# PMV2_IBV1_Altium_page01.net
KiCad netlist of a schematic drawn in Altium Designer
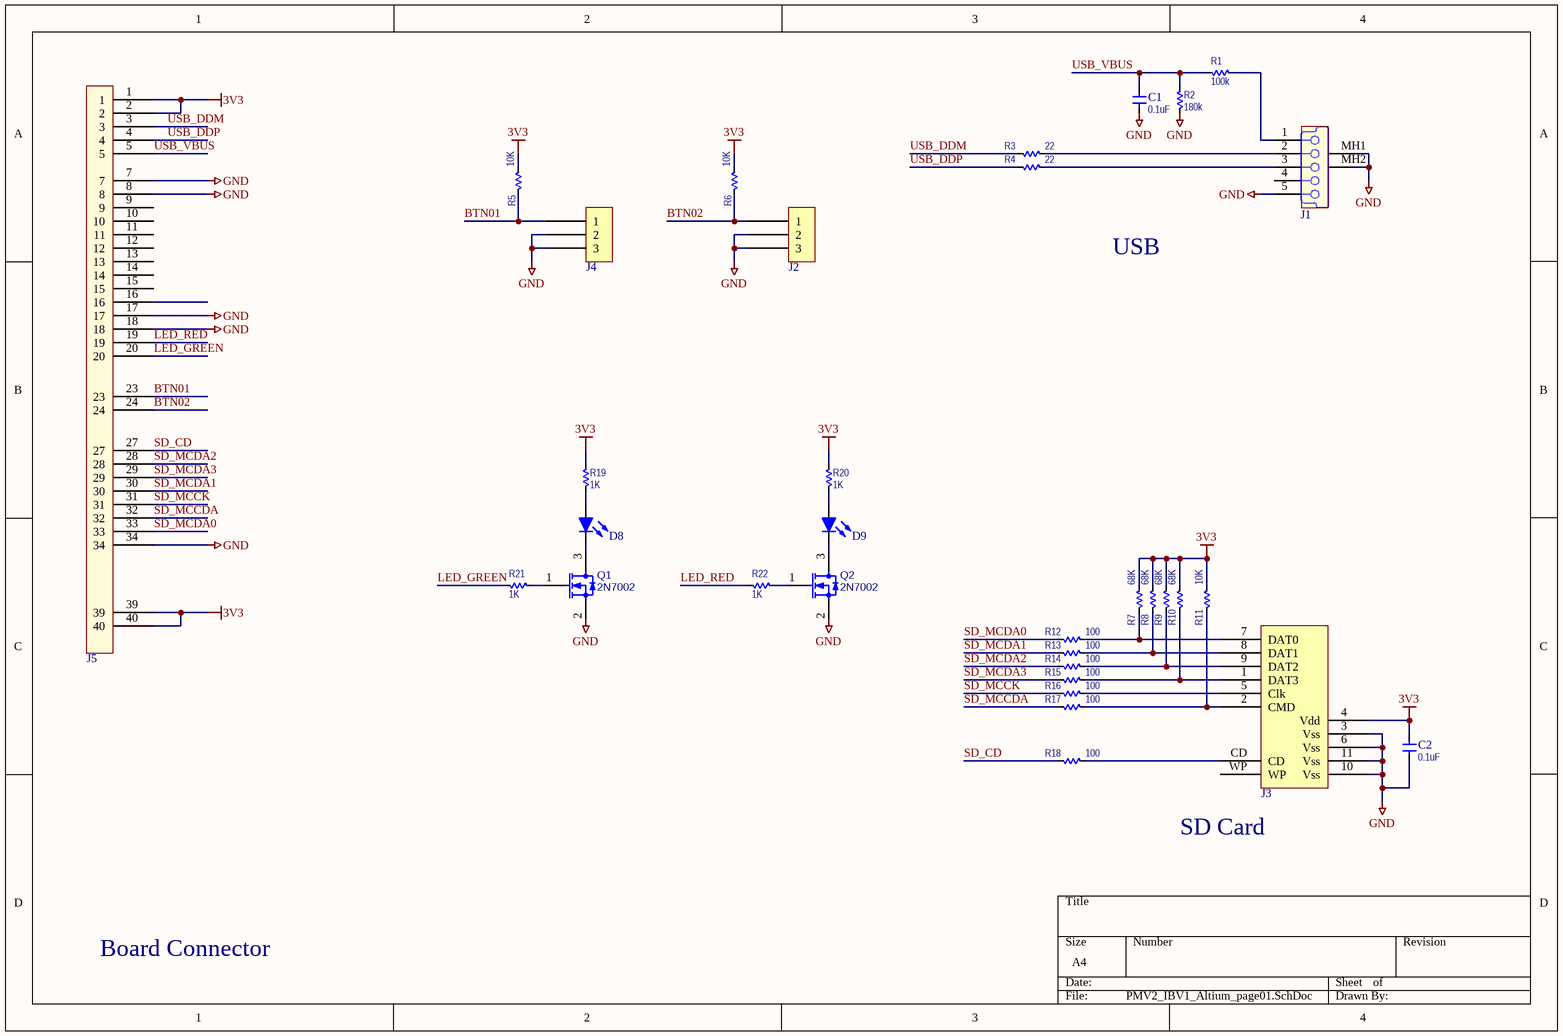
[diagram p0: PMV2_IBV1_Altium_page01.SchDoc]

(export (version "E")
  (design (tool "Eeschema 10.0.6"))
  (components
    (comp (ref "C1")
      (value "0.1uF")
      (footprint "CAPC3216X135N_B")
      (description "CAP CER 0.1UF 25V X7R 1206")
      (fields (field (name "MANUFACTURER") "Kemet") (field (name "DIGIKEY PART NUMBER") "399-5615-1-ND"))
      (libsource (lib "lib_ic_CAP") (part "CAP_C1206F104K3RACTU_KEMET"))
    )
    (comp (ref "C2")
      (value "0.1uF")
      (footprint "CAPC3216X135N_B")
      (description "CAP CER 0.1UF 25V X7R 1206")
      (fields (field (name "MANUFACTURER") "Kemet") (field (name "DIGIKEY PART NUMBER") "399-5615-1-ND"))
      (libsource (lib "lib_ic_CAP") (part "CAP_C1206F104K3RACTU_KEMET"))
    )
    (comp (ref "D8")
      (value "DIO_LED")
      (footprint "Led")
      (description "Diode Led")
      (fields (field (name "PUBLISHER") "Altium Limited"))
      (libsource (lib "lib_ic_DIO") (part "DIO_LED"))
    )
    (comp (ref "D9")
      (value "DIO_LED")
      (footprint "Led")
      (description "Diode Led")
      (fields (field (name "PUBLISHER") "Altium Limited"))
      (libsource (lib "lib_ic_DIO") (part "DIO_LED"))
    )
    (comp (ref "J1")
      (value "CON_MINI_USB")
      (footprint "UBS MiniB")
      (fields
        (field (name "DIGIKEY PART NUMBER") "H11589CT-ND")
        (field (name "MANUFACTURER PART NUMBER") "UX60SC-MB-5S8")
        (field (name "MOUSER PART NUMBER") "798-UX60SC-MB-5S8")
      )
      (libsource (lib "lib_ic_CON") (part "CON_MINI_USB"))
    )
    (comp (ref "J2")
      (value "MSC_Switch")
      (footprint "SW_FSMRA3JH")
      (libsource (lib "lib_ic_MSC") (part "MSC_Switch"))
    )
    (comp (ref "J3")
      (value "CON_SD_Socket")
      (footprint "SD CARD SOCKET")
      (description "SD Socket")
      (fields
        (field (name "DIGIKEY PART NUMBER") "609-3956-1-ND")
        (field (name "MANUFACTURER PART NUMBER") "10067847-001RLF")
      )
      (libsource (lib "lib_ic_CON") (part "CON_SD_Socket"))
    )
    (comp (ref "J4")
      (value "MSC_Switch")
      (footprint "SW_FSMRA3JH")
      (libsource (lib "lib_ic_MSC") (part "MSC_Switch"))
    )
    (comp (ref "J5")
      (value "CON_Header_2x30_PMV2")
      (footprint "HeaderX70b")
      (libsource (lib "lib_ic_CON") (part "CON_Header_2x30_PMV2"))
    )
    (comp (ref "Q1")
      (value "2N7002")
      (footprint "SOT23-3M")
      (description "MOSFET N-CH 60V 115MA SOT23-3")
      (fields
        (field (name "MOUSER PART NUMBER") "621-2N7002-F")
        (field (name "DIGIKEY PART NUMBER") "2N7002-7-F")
      )
      (libsource (lib "lib_ic_IC") (part "Q_2N7002-7-F_DIODES"))
    )
    (comp (ref "Q2")
      (value "2N7002")
      (footprint "SOT23-3M")
      (description "MOSFET N-CH 60V 115MA SOT23-3")
      (fields
        (field (name "MOUSER PART NUMBER") "621-2N7002-F")
        (field (name "DIGIKEY PART NUMBER") "2N7002-7-F")
      )
      (libsource (lib "lib_ic_IC") (part "Q_2N7002-7-F_DIODES"))
    )
    (comp (ref "R1")
      (value "100k")
      (footprint "RESC3216N")
      (description "RES SMD 100K OHM 5% 1/4W 1206")
      (fields (field (name "MANUFACTURER") "YAGEO") (field (name "DIGIKEY PART NUMBER") "311-100KERCT-ND"))
      (libsource (lib "lib_ic_RES") (part "RES_RC1206JR-07100KL_YAGEO"))
    )
    (comp (ref "R2")
      (value "180k")
      (footprint "RESC3216N")
      (description "RES SMD 180K OHM 5% 1/4W 1206")
      (fields (field (name "MANUFACTURER") "YAGEO") (field (name "DIGIKEY PART NUMBER") "311-180KERCT-ND"))
      (libsource (lib "lib_ic_RES") (part "RES_RC1206JR-07180KL_YAGEO"))
    )
    (comp (ref "R3")
      (value "22")
      (footprint "RESC3216N")
      (description "RES SMD 22 OHM 5% 1/4W 1206")
      (fields (field (name "MANUFACTURER") "YAGEO") (field (name "DIGIKEY PART NUMBER") "311-22ERCT-ND"))
      (libsource (lib "lib_ic_RES") (part "RES_RC1206JR-0722RL_YAGEO"))
    )
    (comp (ref "R4")
      (value "22")
      (footprint "RESC3216N")
      (description "RES SMD 22 OHM 5% 1/4W 1206")
      (fields (field (name "MANUFACTURER") "YAGEO") (field (name "DIGIKEY PART NUMBER") "311-22ERCT-ND"))
      (libsource (lib "lib_ic_RES") (part "RES_RC1206JR-0722RL_YAGEO"))
    )
    (comp (ref "R5")
      (value "10K")
      (footprint "RESC3216N")
      (description "RES SMD 10K OHM 1% 1/4W 1206")
      (fields (field (name "TOLERANCE") "1%") (field (name "MANUFACTURER") "Yageo"))
      (libsource (lib "lib_ic_RES") (part "RES_RC1206FR-0710KL_Yageo"))
    )
    (comp (ref "R6")
      (value "10K")
      (footprint "RESC3216N")
      (description "RES SMD 10K OHM 1% 1/4W 1206")
      (fields (field (name "TOLERANCE") "1%") (field (name "MANUFACTURER") "Yageo"))
      (libsource (lib "lib_ic_RES") (part "RES_RC1206FR-0710KL_Yageo"))
    )
    (comp (ref "R7")
      (value "68K")
      (footprint "RESC3216N")
      (description "RES SMD 68K OHM 5% 1/4W 1206")
      (fields (field (name "TOLERANCE") "5%") (field (name "MANUFACTURER") "Yageo"))
      (libsource (lib "lib_ic_RES") (part "RES_RC1206JR-0768KL_Yageo"))
    )
    (comp (ref "R8")
      (value "68K")
      (footprint "RESC3216N")
      (description "RES SMD 68K OHM 5% 1/4W 1206")
      (fields (field (name "TOLERANCE") "5%") (field (name "MANUFACTURER") "Yageo"))
      (libsource (lib "lib_ic_RES") (part "RES_RC1206JR-0768KL_Yageo"))
    )
    (comp (ref "R9")
      (value "68K")
      (footprint "RESC3216N")
      (description "RES SMD 68K OHM 5% 1/4W 1206")
      (fields (field (name "TOLERANCE") "5%") (field (name "MANUFACTURER") "Yageo"))
      (libsource (lib "lib_ic_RES") (part "RES_RC1206JR-0768KL_Yageo"))
    )
    (comp (ref "R10")
      (value "68K")
      (footprint "RESC3216N")
      (description "RES SMD 68K OHM 5% 1/4W 1206")
      (fields (field (name "TOLERANCE") "5%") (field (name "MANUFACTURER") "Yageo"))
      (libsource (lib "lib_ic_RES") (part "RES_RC1206JR-0768KL_Yageo"))
    )
    (comp (ref "R11")
      (value "10K")
      (footprint "RESC3216N")
      (description "RES SMD 10K OHM 1% 1/4W 1206")
      (fields (field (name "TOLERANCE") "1%") (field (name "MANUFACTURER") "Yageo"))
      (libsource (lib "lib_ic_RES") (part "RES_RC1206FR-0710KL_Yageo"))
    )
    (comp (ref "R12")
      (value "100")
      (footprint "RESC3216N")
      (description "RES SMD 100 OHM 5% 1/4W 1206")
      (fields (field (name "TOLERANCE") "5%") (field (name "MANUFACTURER") "Yageo"))
      (libsource (lib "lib_ic_RES") (part "RES_RC1206JR-07100RL_Yageo"))
    )
    (comp (ref "R13")
      (value "100")
      (footprint "RESC3216N")
      (description "RES SMD 100 OHM 5% 1/4W 1206")
      (fields (field (name "TOLERANCE") "5%") (field (name "MANUFACTURER") "Yageo"))
      (libsource (lib "lib_ic_RES") (part "RES_RC1206JR-07100RL_Yageo"))
    )
    (comp (ref "R14")
      (value "100")
      (footprint "RESC3216N")
      (description "RES SMD 100 OHM 5% 1/4W 1206")
      (fields (field (name "TOLERANCE") "5%") (field (name "MANUFACTURER") "Yageo"))
      (libsource (lib "lib_ic_RES") (part "RES_RC1206JR-07100RL_Yageo"))
    )
    (comp (ref "R15")
      (value "100")
      (footprint "RESC3216N")
      (description "RES SMD 100 OHM 5% 1/4W 1206")
      (fields (field (name "TOLERANCE") "5%") (field (name "MANUFACTURER") "Yageo"))
      (libsource (lib "lib_ic_RES") (part "RES_RC1206JR-07100RL_Yageo"))
    )
    (comp (ref "R16")
      (value "100")
      (footprint "RESC3216N")
      (description "RES SMD 100 OHM 5% 1/4W 1206")
      (fields (field (name "TOLERANCE") "5%") (field (name "MANUFACTURER") "Yageo"))
      (libsource (lib "lib_ic_RES") (part "RES_RC1206JR-07100RL_Yageo"))
    )
    (comp (ref "R17")
      (value "100")
      (footprint "RESC3216N")
      (description "RES SMD 100 OHM 5% 1/4W 1206")
      (fields (field (name "TOLERANCE") "5%") (field (name "MANUFACTURER") "Yageo"))
      (libsource (lib "lib_ic_RES") (part "RES_RC1206JR-07100RL_Yageo"))
    )
    (comp (ref "R18")
      (value "100")
      (footprint "RESC3216N")
      (description "RES SMD 100 OHM 5% 1/4W 1206")
      (fields (field (name "TOLERANCE") "5%") (field (name "MANUFACTURER") "Yageo"))
      (libsource (lib "lib_ic_RES") (part "RES_RC1206JR-07100RL_Yageo"))
    )
    (comp (ref "R19")
      (value "1K")
      (footprint "RESC3216N")
      (description "RES SMD 1K OHM 1% 1/4W 1206")
      (fields (field (name "TOLERANCE") "1%") (field (name "MANUFACTURER") "Yageo"))
      (libsource (lib "lib_ic_RES") (part "RES_RC1206FR-071KL_Yageo"))
    )
    (comp (ref "R20")
      (value "1K")
      (footprint "RESC3216N")
      (description "RES SMD 1K OHM 1% 1/4W 1206")
      (fields (field (name "TOLERANCE") "1%") (field (name "MANUFACTURER") "Yageo"))
      (libsource (lib "lib_ic_RES") (part "RES_RC1206FR-071KL_Yageo"))
    )
    (comp (ref "R21")
      (value "1K")
      (footprint "RESC3216N")
      (description "RES SMD 1K OHM 1% 1/4W 1206")
      (fields (field (name "TOLERANCE") "1%") (field (name "MANUFACTURER") "Yageo"))
      (libsource (lib "lib_ic_RES") (part "RES_RC1206FR-071KL_Yageo"))
    )
    (comp (ref "R22")
      (value "1K")
      (footprint "RESC3216N")
      (description "RES SMD 1K OHM 1% 1/4W 1206")
      (fields (field (name "TOLERANCE") "1%") (field (name "MANUFACTURER") "Yageo"))
      (libsource (lib "lib_ic_RES") (part "RES_RC1206FR-071KL_Yageo"))
    )
  )
  (nets
    (net (code "1") (name "/BTN01") (class "Default")
      (node (ref "J4") (pin "1") (pinfunction "1_1") (pintype "passive"))
      (node (ref "J5") (pin "23") (pinfunction "23_23") (pintype "passive"))
      (node (ref "R5") (pin "1") (pinfunction "T1_1") (pintype "passive"))
    )
    (net (code "2") (name "/BTN02") (class "Default")
      (node (ref "J2") (pin "1") (pinfunction "1_1") (pintype "passive"))
      (node (ref "J5") (pin "24") (pinfunction "24_24") (pintype "passive"))
      (node (ref "R6") (pin "1") (pinfunction "T1_1") (pintype "passive"))
    )
    (net (code "3") (name "/LED_GREEN") (class "Default")
      (node (ref "J5") (pin "20") (pinfunction "20_20") (pintype "passive"))
      (node (ref "R21") (pin "2") (pinfunction "T2_2") (pintype "passive"))
    )
    (net (code "4") (name "/LED_RED") (class "Default")
      (node (ref "J5") (pin "19") (pinfunction "19_19") (pintype "passive"))
      (node (ref "R22") (pin "2") (pinfunction "T2_2") (pintype "passive"))
    )
    (net (code "5") (name "/SD_CD") (class "Default")
      (node (ref "J5") (pin "27") (pinfunction "27_27") (pintype "passive"))
      (node (ref "R18") (pin "2") (pinfunction "T2_2") (pintype "passive"))
    )
    (net (code "6") (name "/SD_MCCDA") (class "Default")
      (node (ref "J5") (pin "32") (pinfunction "32_32") (pintype "passive"))
      (node (ref "R17") (pin "2") (pinfunction "T2_2") (pintype "passive"))
    )
    (net (code "7") (name "/SD_MCCK") (class "Default")
      (node (ref "J5") (pin "31") (pinfunction "31_31") (pintype "passive"))
      (node (ref "R16") (pin "2") (pinfunction "T2_2") (pintype "passive"))
    )
    (net (code "8") (name "/SD_MCDA0") (class "Default")
      (node (ref "J5") (pin "33") (pinfunction "33_33") (pintype "passive"))
      (node (ref "R12") (pin "2") (pinfunction "T2_2") (pintype "passive"))
    )
    (net (code "9") (name "/SD_MCDA1") (class "Default")
      (node (ref "J5") (pin "30") (pinfunction "30_30") (pintype "passive"))
      (node (ref "R13") (pin "2") (pinfunction "T2_2") (pintype "passive"))
    )
    (net (code "10") (name "/SD_MCDA2") (class "Default")
      (node (ref "J5") (pin "28") (pinfunction "28_28") (pintype "passive"))
      (node (ref "R14") (pin "2") (pinfunction "T2_2") (pintype "passive"))
    )
    (net (code "11") (name "/SD_MCDA3") (class "Default")
      (node (ref "J5") (pin "29") (pinfunction "29_29") (pintype "passive"))
      (node (ref "R15") (pin "2") (pinfunction "T2_2") (pintype "passive"))
    )
    (net (code "12") (name "/USB_DDM") (class "Default")
      (node (ref "J5") (pin "3") (pinfunction "3_3") (pintype "passive"))
      (node (ref "R3") (pin "2") (pinfunction "T2_2") (pintype "passive"))
    )
    (net (code "13") (name "/USB_DDP") (class "Default")
      (node (ref "J5") (pin "4") (pinfunction "4_4") (pintype "passive"))
      (node (ref "R4") (pin "2") (pinfunction "T2_2") (pintype "passive"))
    )
    (net (code "14") (name "/USB_VBUS") (class "Default")
      (node (ref "C1") (pin "1") (pinfunction "T1_1") (pintype "passive"))
      (node (ref "J5") (pin "5") (pinfunction "5_5") (pintype "passive"))
      (node (ref "R1") (pin "2") (pinfunction "T2_2") (pintype "passive"))
      (node (ref "R2") (pin "1") (pinfunction "T1_1") (pintype "passive"))
    )
    (net (code "15") (name "3V3") (class "Default")
      (node (ref "C2") (pin "1") (pinfunction "T1_1") (pintype "passive"))
      (node (ref "J3") (pin "4") (pinfunction "Vdd_4") (pintype "passive"))
      (node (ref "J5") (pin "1") (pinfunction "1_1") (pintype "passive"))
      (node (ref "J5") (pin "2") (pinfunction "2_2") (pintype "passive"))
      (node (ref "J5") (pin "39") (pinfunction "39_39") (pintype "passive"))
      (node (ref "J5") (pin "40") (pinfunction "40_40") (pintype "passive"))
      (node (ref "R10") (pin "2") (pinfunction "T2_2") (pintype "passive"))
      (node (ref "R11") (pin "2") (pinfunction "T2_2") (pintype "passive"))
      (node (ref "R19") (pin "2") (pinfunction "T2_2") (pintype "passive"))
      (node (ref "R20") (pin "2") (pinfunction "T2_2") (pintype "passive"))
      (node (ref "R5") (pin "2") (pinfunction "T2_2") (pintype "passive"))
      (node (ref "R6") (pin "2") (pinfunction "T2_2") (pintype "passive"))
      (node (ref "R7") (pin "2") (pinfunction "T2_2") (pintype "passive"))
      (node (ref "R8") (pin "2") (pinfunction "T2_2") (pintype "passive"))
      (node (ref "R9") (pin "2") (pinfunction "T2_2") (pintype "passive"))
    )
    (net (code "16") (name "GND") (class "Default")
      (node (ref "C1") (pin "2") (pinfunction "T2_2") (pintype "passive"))
      (node (ref "C2") (pin "2") (pinfunction "T2_2") (pintype "passive"))
      (node (ref "J1") (pin "5") (pinfunction "5_5") (pintype "passive"))
      (node (ref "J1") (pin "MH1") (pinfunction "MH1_MH1") (pintype "passive"))
      (node (ref "J1") (pin "MH2") (pinfunction "MH2_MH2") (pintype "passive"))
      (node (ref "J2") (pin "2") (pinfunction "2_2") (pintype "passive"))
      (node (ref "J2") (pin "3") (pinfunction "3_3") (pintype "passive"))
      (node (ref "J3") (pin "10") (pinfunction "Vss_10") (pintype "passive"))
      (node (ref "J3") (pin "11") (pinfunction "Vss_11") (pintype "passive"))
      (node (ref "J3") (pin "3") (pinfunction "Vss_3") (pintype "passive"))
      (node (ref "J3") (pin "6") (pinfunction "Vss_6") (pintype "passive"))
      (node (ref "J4") (pin "2") (pinfunction "2_2") (pintype "passive"))
      (node (ref "J4") (pin "3") (pinfunction "3_3") (pintype "passive"))
      (node (ref "J5") (pin "17") (pinfunction "17_17") (pintype "passive"))
      (node (ref "J5") (pin "18") (pinfunction "18_18") (pintype "passive"))
      (node (ref "J5") (pin "34") (pinfunction "34_34") (pintype "passive"))
      (node (ref "J5") (pin "7") (pinfunction "7_7") (pintype "passive"))
      (node (ref "J5") (pin "8") (pinfunction "8_8") (pintype "passive"))
      (node (ref "Q1") (pin "2") (pinfunction "S_2") (pintype "passive"))
      (node (ref "Q2") (pin "2") (pinfunction "S_2") (pintype "passive"))
      (node (ref "R2") (pin "2") (pinfunction "T2_2") (pintype "passive"))
    )
    (net (code "17") (name "Net-(D8-A)") (class "Default")
      (node (ref "D8") (pin "1") (pinfunction "A_1") (pintype "passive"))
      (node (ref "R19") (pin "1") (pinfunction "T1_1") (pintype "passive"))
    )
    (net (code "18") (name "Net-(D8-K)") (class "Default")
      (node (ref "D8") (pin "2") (pinfunction "K_2") (pintype "passive"))
      (node (ref "Q1") (pin "3") (pinfunction "D_3") (pintype "passive"))
    )
    (net (code "19") (name "Net-(D9-A)") (class "Default")
      (node (ref "D9") (pin "1") (pinfunction "A_1") (pintype "passive"))
      (node (ref "R20") (pin "1") (pinfunction "T1_1") (pintype "passive"))
    )
    (net (code "20") (name "Net-(D9-K)") (class "Default")
      (node (ref "D9") (pin "2") (pinfunction "K_2") (pintype "passive"))
      (node (ref "Q2") (pin "3") (pinfunction "D_3") (pintype "passive"))
    )
    (net (code "21") (name "Net-(J3-CMD)") (class "Default")
      (node (ref "J3") (pin "2") (pinfunction "CMD_2") (pintype "passive"))
      (node (ref "R11") (pin "1") (pinfunction "T1_1") (pintype "passive"))
      (node (ref "R17") (pin "1") (pinfunction "T1_1") (pintype "passive"))
    )
    (net (code "22") (name "Net-(J3-Clk)") (class "Default")
      (node (ref "J3") (pin "5") (pinfunction "Clk_5") (pintype "passive"))
      (node (ref "R16") (pin "1") (pinfunction "T1_1") (pintype "passive"))
    )
    (net (code "23") (name "Net-(J3-DAT0)") (class "Default")
      (node (ref "J3") (pin "7") (pinfunction "DAT0_7") (pintype "passive"))
      (node (ref "R12") (pin "1") (pinfunction "T1_1") (pintype "passive"))
      (node (ref "R7") (pin "1") (pinfunction "T1_1") (pintype "passive"))
    )
    (net (code "24") (name "Net-(J3-DAT1)") (class "Default")
      (node (ref "J3") (pin "8") (pinfunction "DAT1_8") (pintype "passive"))
      (node (ref "R13") (pin "1") (pinfunction "T1_1") (pintype "passive"))
      (node (ref "R8") (pin "1") (pinfunction "T1_1") (pintype "passive"))
    )
    (net (code "25") (name "Net-(J3-DAT2)") (class "Default")
      (node (ref "J3") (pin "9") (pinfunction "DAT2_9") (pintype "passive"))
      (node (ref "R14") (pin "1") (pinfunction "T1_1") (pintype "passive"))
      (node (ref "R9") (pin "1") (pinfunction "T1_1") (pintype "passive"))
    )
    (net (code "26") (name "Net-(J3-DAT3)") (class "Default")
      (node (ref "J3") (pin "1") (pinfunction "DAT3_1") (pintype "passive"))
      (node (ref "R10") (pin "1") (pinfunction "T1_1") (pintype "passive"))
      (node (ref "R15") (pin "1") (pinfunction "T1_1") (pintype "passive"))
    )
    (net (code "27") (name "Net-(Q1-G)") (class "Default")
      (node (ref "Q1") (pin "1") (pinfunction "G_1") (pintype "passive"))
      (node (ref "R21") (pin "1") (pinfunction "T1_1") (pintype "passive"))
    )
    (net (code "28") (name "Net-(Q2-G)") (class "Default")
      (node (ref "Q2") (pin "1") (pinfunction "G_1") (pintype "passive"))
      (node (ref "R22") (pin "1") (pinfunction "T1_1") (pintype "passive"))
    )
    (net (code "29") (name "Net-(R1-T1)") (class "Default")
      (node (ref "J1") (pin "1") (pinfunction "1_1") (pintype "passive"))
      (node (ref "R1") (pin "1") (pinfunction "T1_1") (pintype "passive"))
    )
    (net (code "30") (name "Net-(R3-T1)") (class "Default")
      (node (ref "J1") (pin "2") (pinfunction "2_2") (pintype "passive"))
      (node (ref "R3") (pin "1") (pinfunction "T1_1") (pintype "passive"))
    )
    (net (code "31") (name "Net-(R4-T1)") (class "Default")
      (node (ref "J1") (pin "3") (pinfunction "3_3") (pintype "passive"))
      (node (ref "R4") (pin "1") (pinfunction "T1_1") (pintype "passive"))
    )
    (net (code "32") (name "Net-(R18-T1)") (class "Default")
      (node (ref "J3") (pin "CD") (pinfunction "CD_CD") (pintype "passive"))
      (node (ref "R18") (pin "1") (pinfunction "T1_1") (pintype "passive"))
    )
    (net (code "33") (name "unconnected-(J1-Pad4)") (class "Default")
      (node (ref "J1") (pin "4") (pinfunction "4_4") (pintype "passive"))
    )
    (net (code "34") (name "unconnected-(J3-PadWP)") (class "Default")
      (node (ref "J3") (pin "WP") (pinfunction "WP_WP") (pintype "passive"))
    )
    (net (code "35") (name "unconnected-(J5-Pad9)") (class "Default")
      (node (ref "J5") (pin "9") (pinfunction "9_9") (pintype "passive"))
    )
    (net (code "36") (name "unconnected-(J5-Pad10)") (class "Default")
      (node (ref "J5") (pin "10") (pinfunction "10_10") (pintype "passive"))
    )
    (net (code "37") (name "unconnected-(J5-Pad11)") (class "Default")
      (node (ref "J5") (pin "11") (pinfunction "11_11") (pintype "passive"))
    )
    (net (code "38") (name "unconnected-(J5-Pad12)") (class "Default")
      (node (ref "J5") (pin "12") (pinfunction "12_12") (pintype "passive"))
    )
    (net (code "39") (name "unconnected-(J5-Pad13)") (class "Default")
      (node (ref "J5") (pin "13") (pinfunction "13_13") (pintype "passive"))
    )
    (net (code "40") (name "unconnected-(J5-Pad14)") (class "Default")
      (node (ref "J5") (pin "14") (pinfunction "14_14") (pintype "passive"))
    )
    (net (code "41") (name "unconnected-(J5-Pad15)") (class "Default")
      (node (ref "J5") (pin "15") (pinfunction "15_15") (pintype "passive"))
    )
    (net (code "42") (name "unconnected-(J5-Pad16)") (class "Default")
      (node (ref "J5") (pin "16") (pinfunction "16_16") (pintype "passive"))
    )
  )
)
